# isoDebug-Isolation.net
KiCad netlist of a schematic drawn in Altium Designer
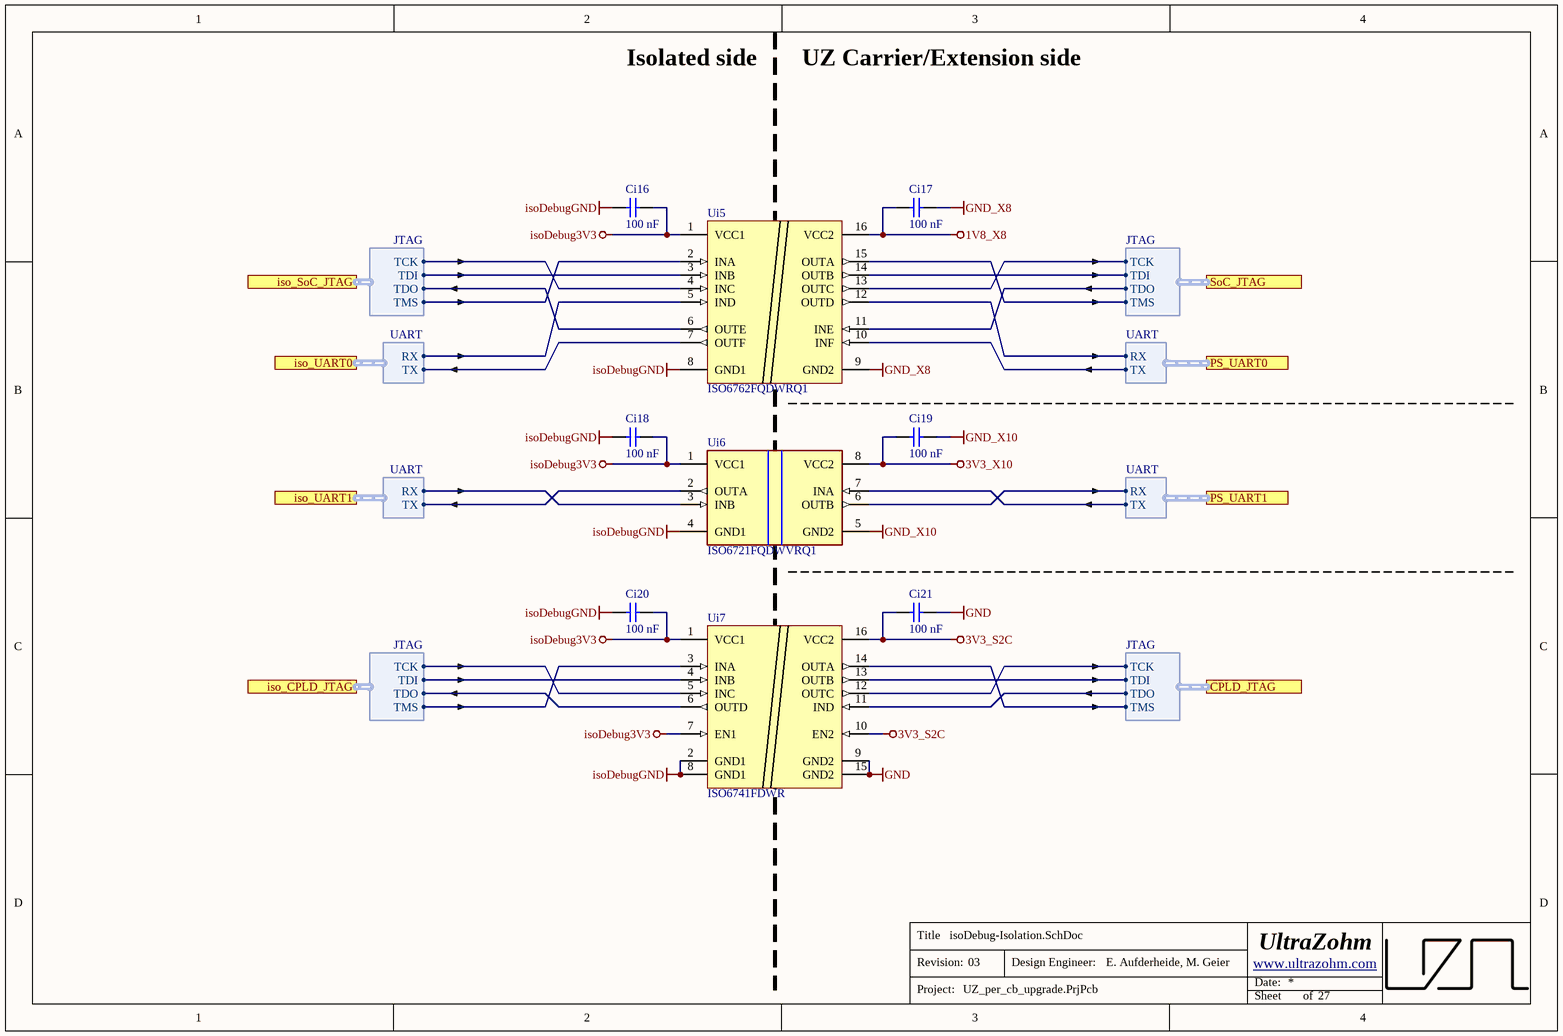
[diagram p0: isoDebug-Isolation.SchDoc]

(export (version "E")
  (design (tool "Eeschema 10.0.6"))
  (components
    (comp (ref "Ci16")
      (value "100 nF")
      (footprint "C_0402_TE")
      (description "Generic capacitor")
      (fields
        (field (name "MANUFACTURER PART NUMBER") "UZgen_C_0402_100nF_50V_X7R")
        (field (name "MANUFACTURER") "UZgen")
        (field (name "CREATED FROM") "UZgenTool")
      )
      (libsource (lib "user") (part "CAP-NP"))
    )
    (comp (ref "Ci17")
      (value "100 nF")
      (footprint "C_0402_TE")
      (description "Generic capacitor")
      (fields
        (field (name "MANUFACTURER PART NUMBER") "UZgen_C_0402_100nF_50V_X7R")
        (field (name "MANUFACTURER") "UZgen")
        (field (name "CREATED FROM") "UZgenTool")
      )
      (libsource (lib "user") (part "CAP-NP"))
    )
    (comp (ref "Ci18")
      (value "100 nF")
      (footprint "C_0402_TE")
      (description "Generic capacitor")
      (fields
        (field (name "MANUFACTURER PART NUMBER") "UZgen_C_0402_100nF_50V_X7R")
        (field (name "MANUFACTURER") "UZgen")
        (field (name "CREATED FROM") "UZgenTool")
      )
      (libsource (lib "user") (part "CAP-NP"))
    )
    (comp (ref "Ci19")
      (value "100 nF")
      (footprint "C_0402_TE")
      (description "Generic capacitor")
      (fields
        (field (name "MANUFACTURER PART NUMBER") "UZgen_C_0402_100nF_50V_X7R")
        (field (name "MANUFACTURER") "UZgen")
        (field (name "CREATED FROM") "UZgenTool")
      )
      (libsource (lib "user") (part "CAP-NP"))
    )
    (comp (ref "Ci20")
      (value "100 nF")
      (footprint "C_0402_TE")
      (description "Generic capacitor")
      (fields
        (field (name "MANUFACTURER PART NUMBER") "UZgen_C_0402_100nF_50V_X7R")
        (field (name "MANUFACTURER") "UZgen")
        (field (name "CREATED FROM") "UZgenTool")
      )
      (libsource (lib "user") (part "CAP-NP"))
    )
    (comp (ref "Ci21")
      (value "100 nF")
      (footprint "C_0402_TE")
      (description "Generic capacitor")
      (fields
        (field (name "MANUFACTURER PART NUMBER") "UZgen_C_0402_100nF_50V_X7R")
        (field (name "MANUFACTURER") "UZgen")
        (field (name "CREATED FROM") "UZgenTool")
      )
      (libsource (lib "user") (part "CAP-NP"))
    )
    (comp (ref "Ui5")
      (value "ISO6762FQDWRQ1")
      (footprint "SOIC127P1030X265-16N")
      (description "ISO676x General-Purpose Six-Channel Reinforced Digital Isolators with Robust EMC")
      (fields
        (field (name "MANUFACTURER") "Texas Instruments")
        (field (name "LCSC PART NUMBER") "C5216383")
        (field (name "CREATED FROM") "FRosner")
      )
      (libsource (lib "user") (part "ISO6762"))
    )
    (comp (ref "Ui6")
      (value "ISO6721FQDWVRQ1")
      (footprint "FP-DWV0008A-IPC_A")
      (description "General Purpose Reinforced and Basic Dual-Channel Automotive Digital Isolators with Robust EMC")
      (fields
        (field (name "MANUFACTURER") "Texas Instruments")
        (field (name "LCSC PART NUMBER") "C5216428")
        (field (name "CREATED FROM") "FRosner")
      )
      (libsource (lib "user") (part "ISO6721DWV"))
    )
    (comp (ref "Ui7")
      (value "ISO6741FDWR")
      (footprint "SOIC127P1030X265-16N")
      (description "Digital Isolators General-purpose, quad-channel, 3/1 digital isolator 16-SOIC -40 to 125")
      (fields
        (field (name "MANUFACTURER") "Texas Instruments")
        (field (name "LCSC PART NUMBER") "C5216433")
        (field (name "CREATED FROM") "FRosner")
      )
      (libsource (lib "user") (part "ISO6741"))
    )
  )
  (nets
    (net (code "5") (name "1V8_X8") (class "Default")
      (node (ref "Ci17") (pin "2") (pinfunction "2_2") (pintype "passive"))
      (node (ref "Ui5") (pin "16") (pinfunction "VCC2_16") (pintype "power_in"))
    )
    (net (code "6") (name "3V3_S2C") (class "Default")
      (node (ref "Ci21") (pin "2") (pinfunction "2_2") (pintype "passive"))
      (node (ref "Ui7") (pin "10") (pinfunction "EN2_10") (pintype "input"))
      (node (ref "Ui7") (pin "16") (pinfunction "VCC2_16") (pintype "power_in"))
    )
    (net (code "7") (name "3V3_X10") (class "Default")
      (node (ref "Ci19") (pin "2") (pinfunction "2_2") (pintype "passive"))
      (node (ref "Ui6") (pin "8") (pinfunction "VCC2_8") (pintype "power_in"))
    )
    (net (code "8") (name "GND") (class "Default")
      (node (ref "Ci21") (pin "1") (pinfunction "1_1") (pintype "passive"))
      (node (ref "Ui7") (pin "15") (pinfunction "GND2_15") (pintype "power_in"))
      (node (ref "Ui7") (pin "9") (pinfunction "GND2_9") (pintype "power_in"))
    )
    (net (code "9") (name "GND_X8") (class "Default")
      (node (ref "Ci17") (pin "1") (pinfunction "1_1") (pintype "passive"))
      (node (ref "Ui5") (pin "9") (pinfunction "GND2_9") (pintype "power_in"))
    )
    (net (code "10") (name "GND_X10") (class "Default")
      (node (ref "Ci19") (pin "1") (pinfunction "1_1") (pintype "passive"))
      (node (ref "Ui6") (pin "5") (pinfunction "GND2_5") (pintype "power_in"))
    )
    (net (code "11") (name "isoDebug3V3") (class "Default")
      (node (ref "Ci16") (pin "1") (pinfunction "1_1") (pintype "passive"))
      (node (ref "Ci18") (pin "1") (pinfunction "1_1") (pintype "passive"))
      (node (ref "Ci20") (pin "1") (pinfunction "1_1") (pintype "passive"))
      (node (ref "Ui5") (pin "1") (pinfunction "VCC1_1") (pintype "power_in"))
      (node (ref "Ui6") (pin "1") (pinfunction "VCC1_1") (pintype "power_in"))
      (node (ref "Ui7") (pin "1") (pinfunction "VCC1_1") (pintype "power_in"))
      (node (ref "Ui7") (pin "7") (pinfunction "EN1_7") (pintype "input"))
    )
    (net (code "12") (name "isoDebugGND") (class "Default")
      (node (ref "Ci16") (pin "2") (pinfunction "2_2") (pintype "passive"))
      (node (ref "Ci18") (pin "2") (pinfunction "2_2") (pintype "passive"))
      (node (ref "Ci20") (pin "2") (pinfunction "2_2") (pintype "passive"))
      (node (ref "Ui5") (pin "8") (pinfunction "GND1_8") (pintype "power_in"))
      (node (ref "Ui6") (pin "4") (pinfunction "GND1_4") (pintype "power_in"))
      (node (ref "Ui7") (pin "2") (pinfunction "GND1_2") (pintype "power_in"))
      (node (ref "Ui7") (pin "8") (pinfunction "GND1_8") (pintype "power_in"))
    )
    (net (code "13") (name "unconnected-(Ui5-INA-Pad2)") (class "Default")
      (node (ref "Ui5") (pin "2") (pinfunction "INA_2") (pintype "input"))
    )
    (net (code "14") (name "unconnected-(Ui5-INB-Pad3)") (class "Default")
      (node (ref "Ui5") (pin "3") (pinfunction "INB_3") (pintype "input"))
    )
    (net (code "15") (name "unconnected-(Ui5-INC-Pad4)") (class "Default")
      (node (ref "Ui5") (pin "4") (pinfunction "INC_4") (pintype "input"))
    )
    (net (code "16") (name "unconnected-(Ui5-IND-Pad5)") (class "Default")
      (node (ref "Ui5") (pin "5") (pinfunction "IND_5") (pintype "input"))
    )
    (net (code "17") (name "unconnected-(Ui5-INE-Pad11)") (class "Default")
      (node (ref "Ui5") (pin "11") (pinfunction "INE_11") (pintype "input"))
    )
    (net (code "18") (name "unconnected-(Ui5-INF-Pad10)") (class "Default")
      (node (ref "Ui5") (pin "10") (pinfunction "INF_10") (pintype "input"))
    )
    (net (code "19") (name "unconnected-(Ui5-OUTA-Pad15)") (class "Default")
      (node (ref "Ui5") (pin "15") (pinfunction "OUTA_15") (pintype "output"))
    )
    (net (code "20") (name "unconnected-(Ui5-OUTB-Pad14)") (class "Default")
      (node (ref "Ui5") (pin "14") (pinfunction "OUTB_14") (pintype "output"))
    )
    (net (code "21") (name "unconnected-(Ui5-OUTC-Pad13)") (class "Default")
      (node (ref "Ui5") (pin "13") (pinfunction "OUTC_13") (pintype "output"))
    )
    (net (code "22") (name "unconnected-(Ui5-OUTD-Pad12)") (class "Default")
      (node (ref "Ui5") (pin "12") (pinfunction "OUTD_12") (pintype "output"))
    )
    (net (code "23") (name "unconnected-(Ui5-OUTE-Pad6)") (class "Default")
      (node (ref "Ui5") (pin "6") (pinfunction "OUTE_6") (pintype "output"))
    )
    (net (code "24") (name "unconnected-(Ui5-OUTF-Pad7)") (class "Default")
      (node (ref "Ui5") (pin "7") (pinfunction "OUTF_7") (pintype "output"))
    )
    (net (code "25") (name "unconnected-(Ui6-INA-Pad7)") (class "Default")
      (node (ref "Ui6") (pin "7") (pinfunction "INA_7") (pintype "input"))
    )
    (net (code "26") (name "unconnected-(Ui6-INB-Pad3)") (class "Default")
      (node (ref "Ui6") (pin "3") (pinfunction "INB_3") (pintype "input"))
    )
    (net (code "27") (name "unconnected-(Ui6-OUTA-Pad2)") (class "Default")
      (node (ref "Ui6") (pin "2") (pinfunction "OUTA_2") (pintype "output"))
    )
    (net (code "28") (name "unconnected-(Ui6-OUTB-Pad6)") (class "Default")
      (node (ref "Ui6") (pin "6") (pinfunction "OUTB_6") (pintype "output"))
    )
    (net (code "29") (name "unconnected-(Ui7-INA-Pad3)") (class "Default")
      (node (ref "Ui7") (pin "3") (pinfunction "INA_3") (pintype "input"))
    )
    (net (code "30") (name "unconnected-(Ui7-INB-Pad4)") (class "Default")
      (node (ref "Ui7") (pin "4") (pinfunction "INB_4") (pintype "input"))
    )
    (net (code "31") (name "unconnected-(Ui7-INC-Pad5)") (class "Default")
      (node (ref "Ui7") (pin "5") (pinfunction "INC_5") (pintype "input"))
    )
    (net (code "32") (name "unconnected-(Ui7-IND-Pad11)") (class "Default")
      (node (ref "Ui7") (pin "11") (pinfunction "IND_11") (pintype "input"))
    )
    (net (code "33") (name "unconnected-(Ui7-OUTA-Pad14)") (class "Default")
      (node (ref "Ui7") (pin "14") (pinfunction "OUTA_14") (pintype "output"))
    )
    (net (code "34") (name "unconnected-(Ui7-OUTB-Pad13)") (class "Default")
      (node (ref "Ui7") (pin "13") (pinfunction "OUTB_13") (pintype "output"))
    )
    (net (code "35") (name "unconnected-(Ui7-OUTC-Pad12)") (class "Default")
      (node (ref "Ui7") (pin "12") (pinfunction "OUTC_12") (pintype "output"))
    )
    (net (code "36") (name "unconnected-(Ui7-OUTD-Pad6)") (class "Default")
      (node (ref "Ui7") (pin "6") (pinfunction "OUTD_6") (pintype "output"))
    )
  )
)
